# Middle_TID_B.net
KiCad netlist of a schematic drawn in Altium Designer
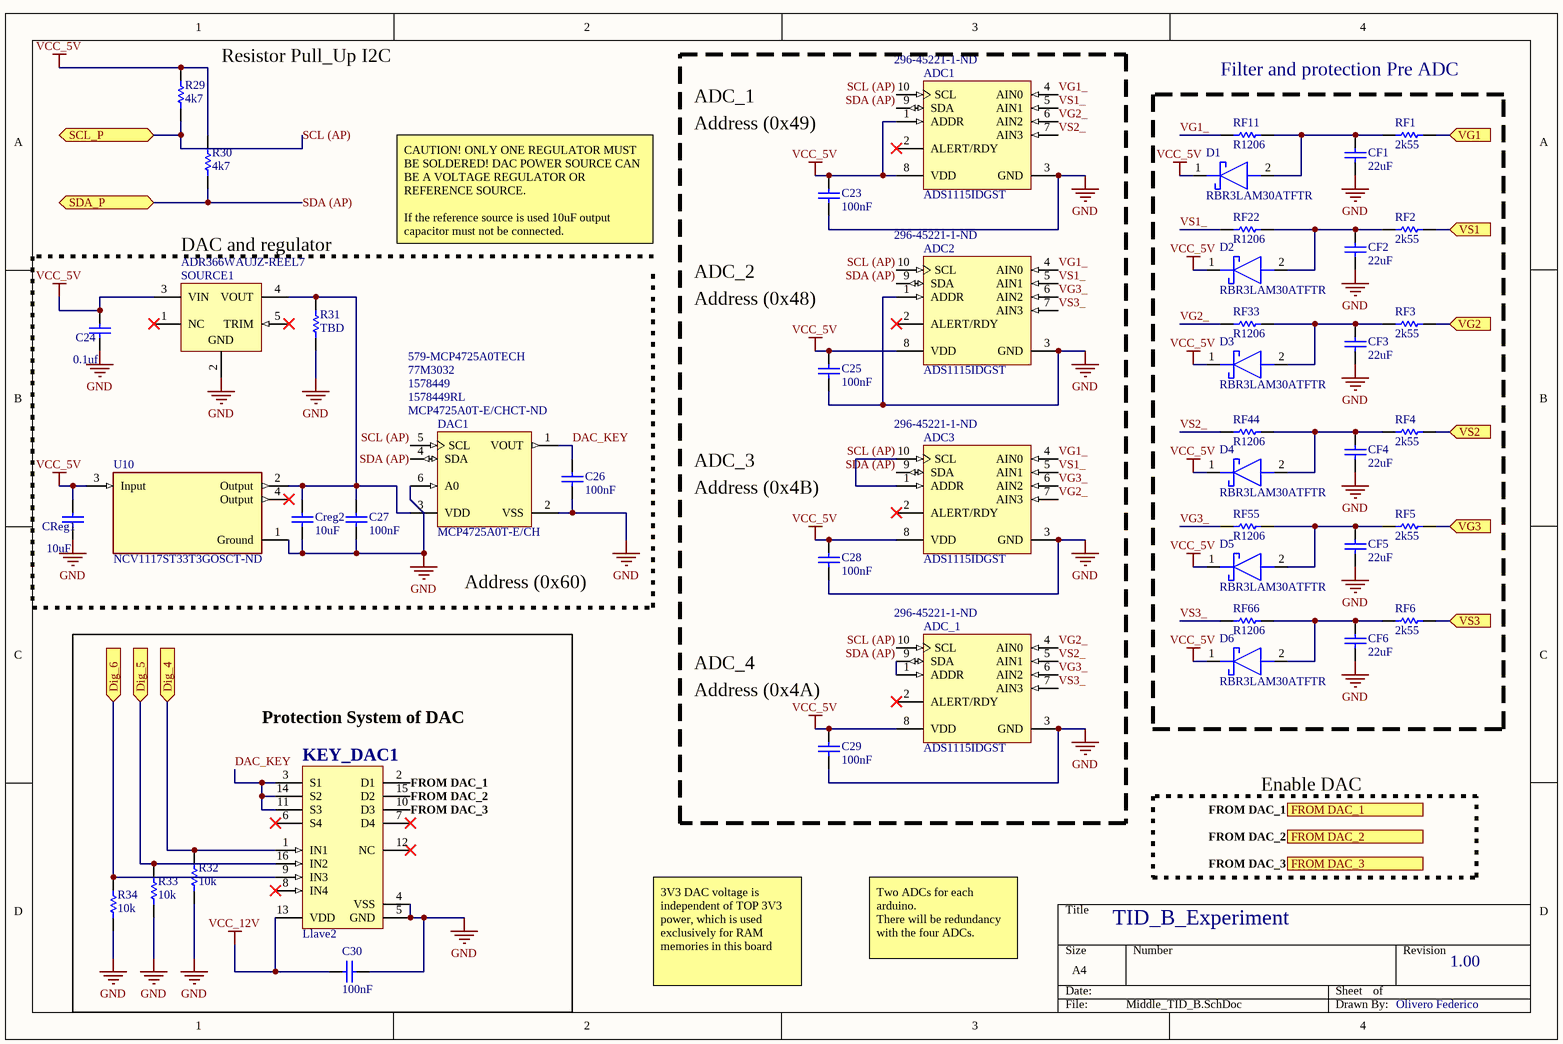
[diagram p0: Middle_TID_B.SchDoc]

(export (version "E")
  (design (tool "Eeschema 10.0.6"))
  (components
    (comp (ref "ADC1")
      (value "ADS1115IDGST")
      (footprint "TI-DGS10_N")
      (fields
        (field (name "MANUFACTURER") "Texas Instruments")
        (field (name "SUPPLIER PART NUMBER 1") "296-45221-1-ND")
      )
      (libsource (lib "Middle_Symbols") (part "ADS1115IDGST"))
    )
    (comp (ref "ADC2")
      (value "ADS1115IDGST")
      (footprint "TI-DGS10_N")
      (fields
        (field (name "MANUFACTURER") "Texas Instruments")
        (field (name "SUPPLIER PART NUMBER 1") "296-45221-1-ND")
      )
      (libsource (lib "Middle_Symbols") (part "ADS1115IDGST"))
    )
    (comp (ref "ADC3")
      (value "ADS1115IDGST")
      (footprint "TI-DGS10_N")
      (fields
        (field (name "MANUFACTURER") "Texas Instruments")
        (field (name "SUPPLIER PART NUMBER 1") "296-45221-1-ND")
      )
      (libsource (lib "Middle_Symbols") (part "ADS1115IDGST"))
    )
    (comp (ref "ADC_1")
      (value "ADS1115IDGST")
      (footprint "TI-DGS10_N")
      (fields
        (field (name "MANUFACTURER") "Texas Instruments")
        (field (name "SUPPLIER PART NUMBER 1") "296-45221-1-ND")
      )
      (libsource (lib "Middle_Symbols") (part "ADS1115IDGST"))
    )
    (comp (ref "C23")
      (value "100nF")
      (footprint "C1206")
      (description "1206 Capacitor")
      (libsource (lib "Middle_Symbols") (part "C1206"))
    )
    (comp (ref "C24")
      (value "0.1uf")
      (footprint "C1206")
      (description "1206 Capacitor")
      (libsource (lib "Middle_Symbols") (part "C1206"))
    )
    (comp (ref "C25")
      (value "100nF")
      (footprint "C1206")
      (description "1206 Capacitor")
      (libsource (lib "Middle_Symbols") (part "C1206"))
    )
    (comp (ref "C26")
      (value "100nF")
      (footprint "C1206")
      (description "1206 Capacitor")
      (libsource (lib "Middle_Symbols") (part "C1206"))
    )
    (comp (ref "C27")
      (value "100nF")
      (footprint "C1206")
      (description "1206 Capacitor")
      (libsource (lib "Middle_Symbols") (part "C1206"))
    )
    (comp (ref "C28")
      (value "100nF")
      (footprint "C1206")
      (description "1206 Capacitor")
      (libsource (lib "Middle_Symbols") (part "C1206"))
    )
    (comp (ref "C29")
      (value "100nF")
      (footprint "C1206")
      (description "1206 Capacitor")
      (libsource (lib "Middle_Symbols") (part "C1206"))
    )
    (comp (ref "C30")
      (value "100nF")
      (footprint "C1206")
      (description "1206 Capacitor")
      (libsource (lib "Middle_Symbols") (part "C1206"))
    )
    (comp (ref "CF1")
      (value "22uF")
      (footprint "C1206")
      (description "1206 Capacitor")
      (libsource (lib "Middle_Symbols") (part "C1206"))
    )
    (comp (ref "CF2")
      (value "22uF")
      (footprint "C1206")
      (description "1206 Capacitor")
      (libsource (lib "Middle_Symbols") (part "C1206"))
    )
    (comp (ref "CF3")
      (value "22uF")
      (footprint "C1206")
      (description "1206 Capacitor")
      (libsource (lib "Middle_Symbols") (part "C1206"))
    )
    (comp (ref "CF4")
      (value "22uF")
      (footprint "C1206")
      (description "1206 Capacitor")
      (libsource (lib "Middle_Symbols") (part "C1206"))
    )
    (comp (ref "CF5")
      (value "22uF")
      (footprint "C1206")
      (description "1206 Capacitor")
      (libsource (lib "Middle_Symbols") (part "C1206"))
    )
    (comp (ref "CF6")
      (value "22uF")
      (footprint "C1206")
      (description "1206 Capacitor")
      (libsource (lib "Middle_Symbols") (part "C1206"))
    )
    (comp (ref "CReg1")
      (value "10uF")
      (footprint "C1206")
      (description "1206 Capacitor")
      (libsource (lib "Middle_Symbols") (part "C1206"))
    )
    (comp (ref "Creg2")
      (value "10uF")
      (footprint "C1206")
      (description "1206 Capacitor")
      (libsource (lib "Middle_Symbols") (part "C1206"))
    )
    (comp (ref "D1")
      (value "RBR3LAM30ATFTR")
      (footprint "SamacSys:SODFL4725X105N")
      (description "Schottky Diode")
      (fields (field (name "MOUSER PART NUMBER") "755-RBR3LAM30ATFTR"))
      (libsource (lib "Middle_Symbols") (part "RBR3LAM30ATFTR"))
    )
    (comp (ref "D2")
      (value "RBR3LAM30ATFTR")
      (footprint "SamacSys:SODFL4725X105N")
      (description "Schottky Diode")
      (fields (field (name "MOUSER PART NUMBER") "755-RBR3LAM30ATFTR"))
      (libsource (lib "Middle_Symbols") (part "RBR3LAM30ATFTR"))
    )
    (comp (ref "D3")
      (value "RBR3LAM30ATFTR")
      (footprint "SamacSys:SODFL4725X105N")
      (description "Schottky Diode")
      (fields (field (name "MOUSER PART NUMBER") "755-RBR3LAM30ATFTR"))
      (libsource (lib "Middle_Symbols") (part "RBR3LAM30ATFTR"))
    )
    (comp (ref "D4")
      (value "RBR3LAM30ATFTR")
      (footprint "SamacSys:SODFL4725X105N")
      (description "Schottky Diode")
      (fields (field (name "MOUSER PART NUMBER") "755-RBR3LAM30ATFTR"))
      (libsource (lib "Middle_Symbols") (part "RBR3LAM30ATFTR"))
    )
    (comp (ref "D5")
      (value "RBR3LAM30ATFTR")
      (footprint "SamacSys:SODFL4725X105N")
      (description "Schottky Diode")
      (fields (field (name "MOUSER PART NUMBER") "755-RBR3LAM30ATFTR"))
      (libsource (lib "Middle_Symbols") (part "RBR3LAM30ATFTR"))
    )
    (comp (ref "D6")
      (value "RBR3LAM30ATFTR")
      (footprint "SamacSys:SODFL4725X105N")
      (description "Schottky Diode")
      (fields (field (name "MOUSER PART NUMBER") "755-RBR3LAM30ATFTR"))
      (libsource (lib "Middle_Symbols") (part "RBR3LAM30ATFTR"))
    )
    (comp (ref "DAC1")
      (value "MCP4725A0T-E/CH")
      (footprint "SOT-23-CH6_N")
      (fields
        (field (name "MANUFACTURER") "Microchip")
        (field (name "SUPPLIER PART NUMBER 1") "MCP4725A0T-E/CHCT-ND")
        (field (name "SUPPLIER PART NUMBER 2") "1578449RL")
        (field (name "SUPPLIER PART NUMBER 3") "1578449")
        (field (name "SUPPLIER PART NUMBER 4") "77M3032")
        (field (name "SUPPLIER PART NUMBER 5") "579-MCP4725A0TECH")
      )
      (libsource (lib "Schlib1") (part "MCP4725A0T-E/CH"))
    )
    (comp (ref "KEY_DAC1")
      (value "Llave2")
      (footprint "ADI-RU-16_N")
      (description "High Voltage Latch-Up Proof, Quad SPST Switches, -40 to 125 degC, 16-pin SOP (RU-16), Tube")
      (fields (field (name "MANUFACTURER") "Analog Devices") (field (name "PARTNUMBER") "ADG5412BRUZ"))
      (libsource (lib "Schlib1") (part "ADG5412BRUZ"))
    )
    (comp (ref "R29")
      (value "4k7")
      (footprint "R1206")
      (description "1206 Resistor")
      (libsource (lib "Middle_Symbols") (part "R1206"))
    )
    (comp (ref "R30")
      (value "4k7")
      (footprint "R1206")
      (description "1206 Resistor")
      (libsource (lib "Middle_Symbols") (part "R1206"))
    )
    (comp (ref "R31")
      (value "TBD")
      (footprint "R1206")
      (description "1206 Resistor")
      (libsource (lib "Middle_Symbols") (part "R1206"))
    )
    (comp (ref "R32")
      (value "10k")
      (footprint "R1206")
      (description "1206 Resistor")
      (libsource (lib "Middle_Symbols") (part "R1206"))
    )
    (comp (ref "R33")
      (value "10k")
      (footprint "R1206")
      (description "1206 Resistor")
      (libsource (lib "Middle_Symbols") (part "R1206"))
    )
    (comp (ref "R34")
      (value "10k")
      (footprint "R1206")
      (description "1206 Resistor")
      (libsource (lib "Middle_Symbols") (part "R1206"))
    )
    (comp (ref "RF1")
      (value "2k55")
      (footprint "R1206")
      (description "1206 Resistor")
      (libsource (lib "Middle_Symbols") (part "R1206"))
    )
    (comp (ref "RF2")
      (value "2k55")
      (footprint "R1206")
      (description "1206 Resistor")
      (libsource (lib "Middle_Symbols") (part "R1206"))
    )
    (comp (ref "RF3")
      (value "2k55")
      (footprint "R1206")
      (description "1206 Resistor")
      (libsource (lib "Middle_Symbols") (part "R1206"))
    )
    (comp (ref "RF4")
      (value "2k55")
      (footprint "R1206")
      (description "1206 Resistor")
      (libsource (lib "Middle_Symbols") (part "R1206"))
    )
    (comp (ref "RF5")
      (value "2k55")
      (footprint "R1206")
      (description "1206 Resistor")
      (libsource (lib "Middle_Symbols") (part "R1206"))
    )
    (comp (ref "RF6")
      (value "2k55")
      (footprint "R1206")
      (description "1206 Resistor")
      (libsource (lib "Middle_Symbols") (part "R1206"))
    )
    (comp (ref "RF11")
      (value "R1206")
      (footprint "R1206")
      (description "1206 Resistor")
      (libsource (lib "Middle_Symbols") (part "R1206"))
    )
    (comp (ref "RF22")
      (value "R1206")
      (footprint "R1206")
      (description "1206 Resistor")
      (libsource (lib "Middle_Symbols") (part "R1206"))
    )
    (comp (ref "RF33")
      (value "R1206")
      (footprint "R1206")
      (description "1206 Resistor")
      (libsource (lib "Middle_Symbols") (part "R1206"))
    )
    (comp (ref "RF44")
      (value "R1206")
      (footprint "R1206")
      (description "1206 Resistor")
      (libsource (lib "Middle_Symbols") (part "R1206"))
    )
    (comp (ref "RF55")
      (value "R1206")
      (footprint "R1206")
      (description "1206 Resistor")
      (libsource (lib "Middle_Symbols") (part "R1206"))
    )
    (comp (ref "RF66")
      (value "R1206")
      (footprint "R1206")
      (description "1206 Resistor")
      (libsource (lib "Middle_Symbols") (part "R1206"))
    )
    (comp (ref "SOURCE1")
      (value "ADR366WAUJZ-REEL7")
      (footprint "ADI-UJ-5_M")
      (fields (field (name "MANUFACTURER") "Analog Devices"))
      (libsource (lib "Altium Content Vault") (part "ADI-ADR36X-UJ-5"))
    )
    (comp (ref "U10")
      (value "NCV1117ST33T3GOSCT-ND")
      (footprint "FP-318H-MFG")
      (description "IC REG LINEAR 3.3V 1A SOT223")
      (fields
        (field (name "OCTOPART") "https://octopart.com/ncv1117st33t3g-on+semiconductor-1215835")
        (field (name "MANUFACTURER PART NUMBER") "NCV1117ST33T3G")
      )
      (libsource (lib "Altium Content Vault") (part "fe1c1c19b4622c016f317b32cf6f7fc"))
    )
  )
  (nets
    (net (code "1") (name "/DAC_KEY") (class "Default")
      (node (ref "C26") (pin "2") (pinfunction "2_2") (pintype "passive"))
      (node (ref "DAC1") (pin "1") (pinfunction "VOUT_1") (pintype "output"))
      (node (ref "KEY_DAC1") (pin "11") (pinfunction "S3_11") (pintype "passive"))
      (node (ref "KEY_DAC1") (pin "14") (pinfunction "S2_14") (pintype "passive"))
      (node (ref "KEY_DAC1") (pin "3") (pinfunction "S1_3") (pintype "passive"))
    )
    (net (code "2") (name "/Dig_4") (class "Default")
      (node (ref "KEY_DAC1") (pin "1") (pinfunction "IN1_1") (pintype "input"))
      (node (ref "R32") (pin "2") (pinfunction "2_2") (pintype "passive"))
    )
    (net (code "3") (name "/Dig_5") (class "Default")
      (node (ref "KEY_DAC1") (pin "16") (pinfunction "IN2_16") (pintype "input"))
      (node (ref "R33") (pin "2") (pinfunction "2_2") (pintype "passive"))
    )
    (net (code "4") (name "/Dig_6") (class "Default")
      (node (ref "KEY_DAC1") (pin "9") (pinfunction "IN3_9") (pintype "input"))
      (node (ref "R34") (pin "2") (pinfunction "2_2") (pintype "passive"))
    )
    (net (code "5") (name "/FROM DAC_1") (class "Default")
      (node (ref "KEY_DAC1") (pin "2") (pinfunction "D1_2") (pintype "passive"))
    )
    (net (code "6") (name "/FROM DAC_2") (class "Default")
      (node (ref "KEY_DAC1") (pin "15") (pinfunction "D2_15") (pintype "passive"))
    )
    (net (code "7") (name "/FROM DAC_3") (class "Default")
      (node (ref "KEY_DAC1") (pin "10") (pinfunction "D3_10") (pintype "passive"))
    )
    (net (code "8") (name "/SCL (AP)") (class "Default")
      (node (ref "ADC1") (pin "10") (pinfunction "SCL_10") (pintype "input"))
      (node (ref "ADC2") (pin "10") (pinfunction "SCL_10") (pintype "input"))
      (node (ref "ADC3") (pin "1") (pinfunction "ADDR_1") (pintype "input"))
      (node (ref "ADC3") (pin "10") (pinfunction "SCL_10") (pintype "input"))
      (node (ref "ADC_1") (pin "10") (pinfunction "SCL_10") (pintype "input"))
      (node (ref "DAC1") (pin "5") (pinfunction "SCL_5") (pintype "input"))
      (node (ref "R29") (pin "1") (pinfunction "1_1") (pintype "passive"))
    )
    (net (code "9") (name "/SDA (AP)") (class "Default")
      (node (ref "ADC1") (pin "9") (pinfunction "SDA_9") (pintype "bidirectional"))
      (node (ref "ADC2") (pin "9") (pinfunction "SDA_9") (pintype "bidirectional"))
      (node (ref "ADC3") (pin "9") (pinfunction "SDA_9") (pintype "bidirectional"))
      (node (ref "ADC_1") (pin "1") (pinfunction "ADDR_1") (pintype "input"))
      (node (ref "ADC_1") (pin "9") (pinfunction "SDA_9") (pintype "bidirectional"))
      (node (ref "DAC1") (pin "4") (pinfunction "SDA_4") (pintype "bidirectional"))
      (node (ref "R30") (pin "1") (pinfunction "1_1") (pintype "passive"))
    )
    (net (code "10") (name "/VG1") (class "Default")
      (node (ref "RF1") (pin "2") (pinfunction "2_2") (pintype "passive"))
    )
    (net (code "11") (name "/VG1_") (class "Default")
      (node (ref "ADC1") (pin "4") (pinfunction "AIN0_4") (pintype "input"))
      (node (ref "ADC2") (pin "4") (pinfunction "AIN0_4") (pintype "input"))
      (node (ref "ADC3") (pin "4") (pinfunction "AIN0_4") (pintype "input"))
      (node (ref "RF11") (pin "1") (pinfunction "1_1") (pintype "passive"))
    )
    (net (code "12") (name "/VG2") (class "Default")
      (node (ref "RF3") (pin "2") (pinfunction "2_2") (pintype "passive"))
    )
    (net (code "13") (name "/VG2_") (class "Default")
      (node (ref "ADC1") (pin "6") (pinfunction "AIN2_6") (pintype "input"))
      (node (ref "ADC3") (pin "7") (pinfunction "AIN3_7") (pintype "input"))
      (node (ref "ADC_1") (pin "4") (pinfunction "AIN0_4") (pintype "input"))
      (node (ref "RF33") (pin "1") (pinfunction "1_1") (pintype "passive"))
    )
    (net (code "14") (name "/VG3") (class "Default")
      (node (ref "RF5") (pin "2") (pinfunction "2_2") (pintype "passive"))
    )
    (net (code "15") (name "/VG3_") (class "Default")
      (node (ref "ADC2") (pin "6") (pinfunction "AIN2_6") (pintype "input"))
      (node (ref "ADC3") (pin "6") (pinfunction "AIN2_6") (pintype "input"))
      (node (ref "ADC_1") (pin "6") (pinfunction "AIN2_6") (pintype "input"))
      (node (ref "RF55") (pin "1") (pinfunction "1_1") (pintype "passive"))
    )
    (net (code "16") (name "/VS1") (class "Default")
      (node (ref "RF2") (pin "2") (pinfunction "2_2") (pintype "passive"))
    )
    (net (code "17") (name "/VS1_") (class "Default")
      (node (ref "ADC1") (pin "5") (pinfunction "AIN1_5") (pintype "input"))
      (node (ref "ADC2") (pin "5") (pinfunction "AIN1_5") (pintype "input"))
      (node (ref "ADC3") (pin "5") (pinfunction "AIN1_5") (pintype "input"))
      (node (ref "RF22") (pin "1") (pinfunction "1_1") (pintype "passive"))
    )
    (net (code "18") (name "/VS2") (class "Default")
      (node (ref "RF4") (pin "2") (pinfunction "2_2") (pintype "passive"))
    )
    (net (code "19") (name "/VS2_") (class "Default")
      (node (ref "ADC1") (pin "7") (pinfunction "AIN3_7") (pintype "input"))
      (node (ref "ADC_1") (pin "5") (pinfunction "AIN1_5") (pintype "input"))
      (node (ref "RF44") (pin "1") (pinfunction "1_1") (pintype "passive"))
    )
    (net (code "20") (name "/VS3") (class "Default")
      (node (ref "RF6") (pin "2") (pinfunction "2_2") (pintype "passive"))
    )
    (net (code "21") (name "/VS3_") (class "Default")
      (node (ref "ADC2") (pin "7") (pinfunction "AIN3_7") (pintype "input"))
      (node (ref "ADC_1") (pin "7") (pinfunction "AIN3_7") (pintype "input"))
      (node (ref "RF66") (pin "1") (pinfunction "1_1") (pintype "passive"))
    )
    (net (code "22") (name "GND") (class "Default")
      (node (ref "ADC1") (pin "3") (pinfunction "GND_3") (pintype "power_in"))
      (node (ref "ADC2") (pin "1") (pinfunction "ADDR_1") (pintype "input"))
      (node (ref "ADC2") (pin "3") (pinfunction "GND_3") (pintype "power_in"))
      (node (ref "ADC3") (pin "3") (pinfunction "GND_3") (pintype "power_in"))
      (node (ref "ADC_1") (pin "3") (pinfunction "GND_3") (pintype "power_in"))
      (node (ref "C23") (pin "1") (pinfunction "1_1") (pintype "passive"))
      (node (ref "C24") (pin "2") (pinfunction "2_2") (pintype "passive"))
      (node (ref "C25") (pin "1") (pinfunction "1_1") (pintype "passive"))
      (node (ref "C26") (pin "1") (pinfunction "1_1") (pintype "passive"))
      (node (ref "C27") (pin "1") (pinfunction "1_1") (pintype "passive"))
      (node (ref "C28") (pin "1") (pinfunction "1_1") (pintype "passive"))
      (node (ref "C29") (pin "1") (pinfunction "1_1") (pintype "passive"))
      (node (ref "C30") (pin "1") (pinfunction "1_1") (pintype "passive"))
      (node (ref "CF1") (pin "1") (pinfunction "1_1") (pintype "passive"))
      (node (ref "CF2") (pin "1") (pinfunction "1_1") (pintype "passive"))
      (node (ref "CF3") (pin "1") (pinfunction "1_1") (pintype "passive"))
      (node (ref "CF4") (pin "1") (pinfunction "1_1") (pintype "passive"))
      (node (ref "CF5") (pin "1") (pinfunction "1_1") (pintype "passive"))
      (node (ref "CF6") (pin "1") (pinfunction "1_1") (pintype "passive"))
      (node (ref "CReg1") (pin "2") (pinfunction "2_2") (pintype "passive"))
      (node (ref "Creg2") (pin "1") (pinfunction "1_1") (pintype "passive"))
      (node (ref "DAC1") (pin "2") (pinfunction "VSS_2") (pintype "power_in"))
      (node (ref "DAC1") (pin "6") (pinfunction "A0_6") (pintype "input"))
      (node (ref "KEY_DAC1") (pin "4") (pinfunction "VSS_4") (pintype "power_in"))
      (node (ref "KEY_DAC1") (pin "5") (pinfunction "GND_5") (pintype "power_in"))
      (node (ref "R31") (pin "1") (pinfunction "1_1") (pintype "passive"))
      (node (ref "R32") (pin "1") (pinfunction "1_1") (pintype "passive"))
      (node (ref "R33") (pin "1") (pinfunction "1_1") (pintype "passive"))
      (node (ref "R34") (pin "1") (pinfunction "1_1") (pintype "passive"))
      (node (ref "SOURCE1") (pin "2") (pinfunction "GND_2") (pintype "power_in"))
      (node (ref "U10") (pin "1") (pinfunction "Ground_1") (pintype "power_in"))
    )
    (net (code "23") (name "Net-(D1-A)") (class "Default")
      (node (ref "CF1") (pin "2") (pinfunction "2_2") (pintype "passive"))
      (node (ref "D1") (pin "2") (pinfunction "A_2") (pintype "passive"))
      (node (ref "RF1") (pin "1") (pinfunction "1_1") (pintype "passive"))
      (node (ref "RF11") (pin "2") (pinfunction "2_2") (pintype "passive"))
    )
    (net (code "24") (name "Net-(D2-A)") (class "Default")
      (node (ref "CF2") (pin "2") (pinfunction "2_2") (pintype "passive"))
      (node (ref "D2") (pin "2") (pinfunction "A_2") (pintype "passive"))
      (node (ref "RF2") (pin "1") (pinfunction "1_1") (pintype "passive"))
      (node (ref "RF22") (pin "2") (pinfunction "2_2") (pintype "passive"))
    )
    (net (code "25") (name "Net-(D3-A)") (class "Default")
      (node (ref "CF3") (pin "2") (pinfunction "2_2") (pintype "passive"))
      (node (ref "D3") (pin "2") (pinfunction "A_2") (pintype "passive"))
      (node (ref "RF3") (pin "1") (pinfunction "1_1") (pintype "passive"))
      (node (ref "RF33") (pin "2") (pinfunction "2_2") (pintype "passive"))
    )
    (net (code "26") (name "Net-(D4-A)") (class "Default")
      (node (ref "CF4") (pin "2") (pinfunction "2_2") (pintype "passive"))
      (node (ref "D4") (pin "2") (pinfunction "A_2") (pintype "passive"))
      (node (ref "RF4") (pin "1") (pinfunction "1_1") (pintype "passive"))
      (node (ref "RF44") (pin "2") (pinfunction "2_2") (pintype "passive"))
    )
    (net (code "27") (name "Net-(D5-A)") (class "Default")
      (node (ref "CF5") (pin "2") (pinfunction "2_2") (pintype "passive"))
      (node (ref "D5") (pin "2") (pinfunction "A_2") (pintype "passive"))
      (node (ref "RF5") (pin "1") (pinfunction "1_1") (pintype "passive"))
      (node (ref "RF55") (pin "2") (pinfunction "2_2") (pintype "passive"))
    )
    (net (code "28") (name "Net-(D6-A)") (class "Default")
      (node (ref "CF6") (pin "2") (pinfunction "2_2") (pintype "passive"))
      (node (ref "D6") (pin "2") (pinfunction "A_2") (pintype "passive"))
      (node (ref "RF6") (pin "1") (pinfunction "1_1") (pintype "passive"))
      (node (ref "RF66") (pin "2") (pinfunction "2_2") (pintype "passive"))
    )
    (net (code "29") (name "Net-(DAC1-VDD)") (class "Default")
      (node (ref "C27") (pin "2") (pinfunction "2_2") (pintype "passive"))
      (node (ref "Creg2") (pin "2") (pinfunction "2_2") (pintype "passive"))
      (node (ref "DAC1") (pin "3") (pinfunction "VDD_3") (pintype "power_in"))
      (node (ref "R31") (pin "2") (pinfunction "2_2") (pintype "passive"))
      (node (ref "SOURCE1") (pin "4") (pinfunction "VOUT_4") (pintype "power_in"))
      (node (ref "U10") (pin "2") (pinfunction "Output_2") (pintype "output"))
    )
    (net (code "30") (name "VCC_5V") (class "Default")
      (node (ref "ADC1") (pin "1") (pinfunction "ADDR_1") (pintype "input"))
      (node (ref "ADC1") (pin "8") (pinfunction "VDD_8") (pintype "power_in"))
      (node (ref "ADC2") (pin "8") (pinfunction "VDD_8") (pintype "power_in"))
      (node (ref "ADC3") (pin "8") (pinfunction "VDD_8") (pintype "power_in"))
      (node (ref "ADC_1") (pin "8") (pinfunction "VDD_8") (pintype "power_in"))
      (node (ref "C23") (pin "2") (pinfunction "2_2") (pintype "passive"))
      (node (ref "C24") (pin "1") (pinfunction "1_1") (pintype "passive"))
      (node (ref "C25") (pin "2") (pinfunction "2_2") (pintype "passive"))
      (node (ref "C28") (pin "2") (pinfunction "2_2") (pintype "passive"))
      (node (ref "C29") (pin "2") (pinfunction "2_2") (pintype "passive"))
      (node (ref "CReg1") (pin "1") (pinfunction "1_1") (pintype "passive"))
      (node (ref "D1") (pin "1") (pinfunction "K_1") (pintype "passive"))
      (node (ref "D2") (pin "1") (pinfunction "K_1") (pintype "passive"))
      (node (ref "D3") (pin "1") (pinfunction "K_1") (pintype "passive"))
      (node (ref "D4") (pin "1") (pinfunction "K_1") (pintype "passive"))
      (node (ref "D5") (pin "1") (pinfunction "K_1") (pintype "passive"))
      (node (ref "D6") (pin "1") (pinfunction "K_1") (pintype "passive"))
      (node (ref "R29") (pin "2") (pinfunction "2_2") (pintype "passive"))
      (node (ref "R30") (pin "2") (pinfunction "2_2") (pintype "passive"))
      (node (ref "SOURCE1") (pin "3") (pinfunction "VIN_3") (pintype "power_in"))
      (node (ref "U10") (pin "3") (pinfunction "Input_3") (pintype "input"))
    )
    (net (code "31") (name "VCC_12V") (class "Default")
      (node (ref "C30") (pin "2") (pinfunction "2_2") (pintype "passive"))
      (node (ref "KEY_DAC1") (pin "13") (pinfunction "VDD_13") (pintype "power_in"))
    )
    (net (code "32") (name "unconnected-(ADC1-ALERT{slash}RDY-Pad2)") (class "Default")
      (node (ref "ADC1") (pin "2") (pinfunction "ALERT/RDY_2") (pintype "open_collector+no_connect"))
    )
    (net (code "33") (name "unconnected-(ADC2-ALERT{slash}RDY-Pad2)") (class "Default")
      (node (ref "ADC2") (pin "2") (pinfunction "ALERT/RDY_2") (pintype "open_collector+no_connect"))
    )
    (net (code "34") (name "unconnected-(ADC3-ALERT{slash}RDY-Pad2)") (class "Default")
      (node (ref "ADC3") (pin "2") (pinfunction "ALERT/RDY_2") (pintype "open_collector+no_connect"))
    )
    (net (code "35") (name "unconnected-(ADC_1-ALERT{slash}RDY-Pad2)") (class "Default")
      (node (ref "ADC_1") (pin "2") (pinfunction "ALERT/RDY_2") (pintype "open_collector+no_connect"))
    )
    (net (code "36") (name "unconnected-(KEY_DAC1-D4-Pad7)") (class "Default")
      (node (ref "KEY_DAC1") (pin "7") (pinfunction "D4_7") (pintype "passive+no_connect"))
    )
    (net (code "37") (name "unconnected-(KEY_DAC1-IN4-Pad8)") (class "Default")
      (node (ref "KEY_DAC1") (pin "8") (pinfunction "IN4_8") (pintype "input+no_connect"))
    )
    (net (code "38") (name "unconnected-(KEY_DAC1-NC-Pad12)") (class "Default")
      (node (ref "KEY_DAC1") (pin "12") (pinfunction "NC_12") (pintype "passive+no_connect"))
    )
    (net (code "39") (name "unconnected-(KEY_DAC1-S4-Pad6)") (class "Default")
      (node (ref "KEY_DAC1") (pin "6") (pinfunction "S4_6") (pintype "passive+no_connect"))
    )
    (net (code "40") (name "unconnected-(SOURCE1-NC-Pad1)") (class "Default")
      (node (ref "SOURCE1") (pin "1") (pinfunction "NC_1") (pintype "passive+no_connect"))
    )
    (net (code "41") (name "unconnected-(SOURCE1-TRIM-Pad5)") (class "Default")
      (node (ref "SOURCE1") (pin "5") (pinfunction "TRIM_5") (pintype "input+no_connect"))
    )
    (net (code "42") (name "unconnected-(U10-Output-Pad4)") (class "Default")
      (node (ref "U10") (pin "4") (pinfunction "Output_4") (pintype "output+no_connect"))
    )
  )
)
